# NANO_SIMPLE_walkie-talkie.net
KiCad netlist of a schematic drawn in EAGLE
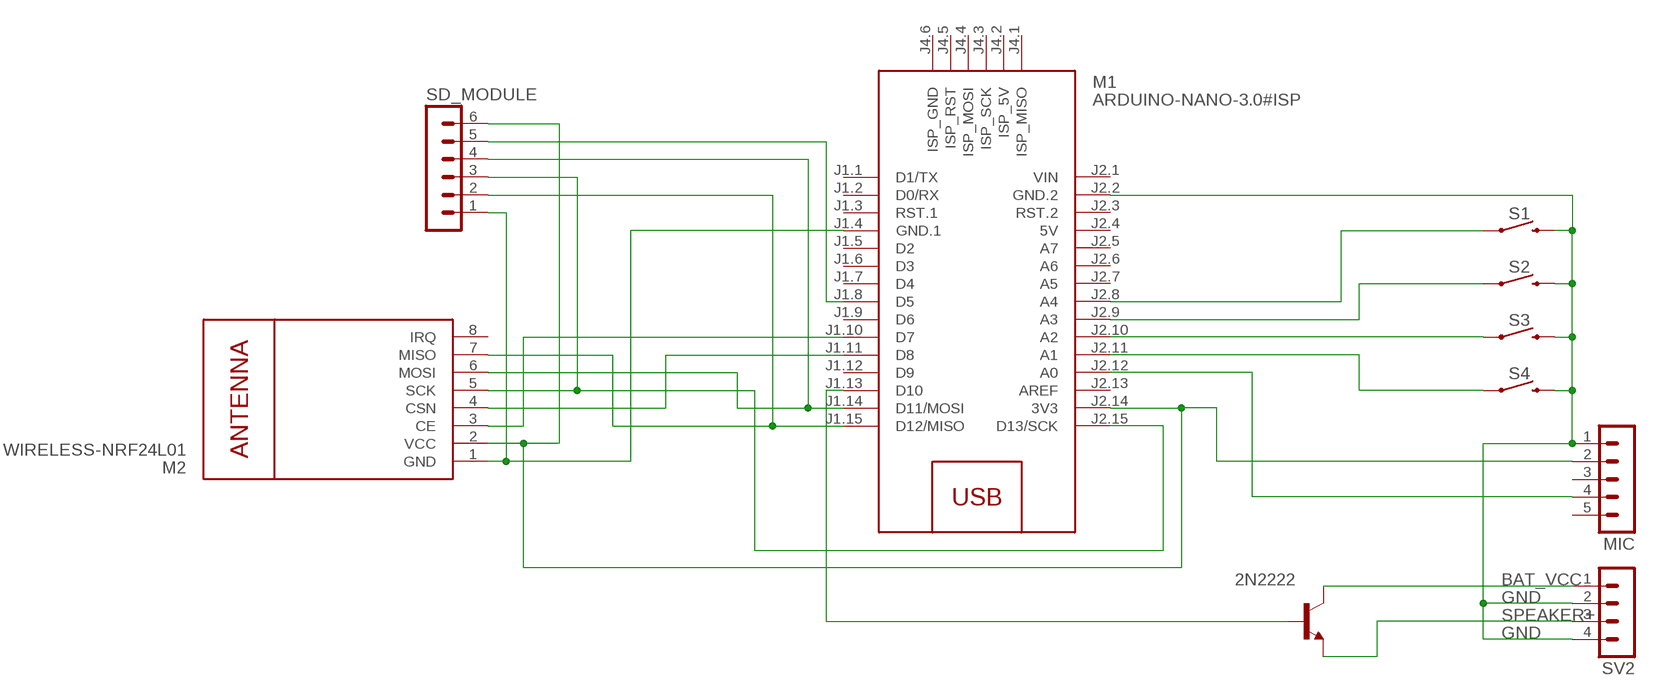
[diagram p0: schematic, sheet 1]

(export (version "E")
  (design (tool "Eeschema 10.0.6"))
  (components
    (comp (ref "M1")
      (value "ARDUINO-NANO-3.0#ISP")
      (footprint "eagle-import:ARDUINO-NANO-3.0#ISP")
      (libsource (lib "eagle-import") (part "ARDUINO-NANO-3.0#ISP"))
    )
    (comp (ref "M2")
      (value "WIRELESS-NRF24L01")
      (footprint "eagle-import:WIRELESS-NRF24L01")
      (libsource (lib "eagle-import") (part "WIRELESS-NRF24L01"))
    )
    (comp (ref "MIC")
      (value "MA05-1")
      (footprint "eagle-import:MA05-1")
      (libsource (lib "eagle-import") (part "MA05-1"))
    )
    (comp (ref "S1")
      (value "MOMENTARY-SWITCH-SPST-PTH-6.0MM")
      (footprint "eagle-import:TACTILE_SWITCH_PTH_6.0MM")
      (libsource (lib "eagle-import") (part "MOMENTARY-SWITCH-SPST-PTH-6.0MM"))
    )
    (comp (ref "S2")
      (value "MOMENTARY-SWITCH-SPST-PTH-6.0MM")
      (footprint "eagle-import:TACTILE_SWITCH_PTH_6.0MM")
      (libsource (lib "eagle-import") (part "MOMENTARY-SWITCH-SPST-PTH-6.0MM"))
    )
    (comp (ref "S3")
      (value "MOMENTARY-SWITCH-SPST-PTH-6.0MM")
      (footprint "eagle-import:TACTILE_SWITCH_PTH_6.0MM")
      (libsource (lib "eagle-import") (part "MOMENTARY-SWITCH-SPST-PTH-6.0MM"))
    )
    (comp (ref "S4")
      (value "MOMENTARY-SWITCH-SPST-PTH-6.0MM")
      (footprint "eagle-import:TACTILE_SWITCH_PTH_6.0MM")
      (libsource (lib "eagle-import") (part "MOMENTARY-SWITCH-SPST-PTH-6.0MM"))
    )
    (comp (ref "SD_MODULE")
      (value "MA06-1")
      (footprint "eagle-import:MA06-1")
      (libsource (lib "eagle-import") (part "MA06-1"))
    )
    (comp (ref "SV2")
      (value "MA04-1")
      (footprint "eagle-import:MA04-1")
      (libsource (lib "eagle-import") (part "MA04-1"))
    )
    (comp (ref "T1")
      (value "2N2222")
      (footprint "eagle-import:TO18")
      (libsource (lib "eagle-import") (part "2N2222"))
    )
  )
  (nets
    (net (code "1") (name "/5V") (class "Default")
      (node (ref "M1") (pin "J2.4") (pinfunction "5V_J2.4") (pintype "power_in"))
    )
    (net (code "2") (name "/BAT_VCC") (class "Default")
      (node (ref "SV2") (pin "1") (pinfunction "1_1") (pintype "passive"))
      (node (ref "T1") (pin "3") (pinfunction "C_3") (pintype "passive"))
    )
    (net (code "3") (name "/GND") (class "Default")
      (node (ref "M1") (pin "J2.2") (pinfunction "GND.2_J2.2") (pintype "power_in"))
      (node (ref "MIC") (pin "1") (pinfunction "1_1") (pintype "passive"))
      (node (ref "S1") (pin "3") (pinfunction "2_3") (pintype "passive"))
      (node (ref "S2") (pin "3") (pinfunction "2_3") (pintype "passive"))
      (node (ref "S3") (pin "3") (pinfunction "2_3") (pintype "passive"))
      (node (ref "S4") (pin "3") (pinfunction "2_3") (pintype "passive"))
      (node (ref "SV2") (pin "2") (pinfunction "2_2") (pintype "passive"))
      (node (ref "SV2") (pin "4") (pinfunction "4_4") (pintype "passive"))
    )
    (net (code "4") (name "/SPEAKER+") (class "Default")
      (node (ref "SV2") (pin "3") (pinfunction "3_3") (pintype "passive"))
      (node (ref "T1") (pin "1") (pinfunction "E_1") (pintype "passive"))
    )
    (net (code "5") (name "/VIN") (class "Default")
      (node (ref "M1") (pin "J2.1") (pinfunction "VIN_J2.1") (pintype "power_in"))
    )
    (net (code "6") (name "Net-(M1-3V3)") (class "Default")
      (node (ref "M1") (pin "J2.14") (pinfunction "3V3_J2.14") (pintype "power_in"))
      (node (ref "M2") (pin "2") (pinfunction "VCC_2") (pintype "power_in"))
      (node (ref "MIC") (pin "2") (pinfunction "2_2") (pintype "passive"))
      (node (ref "SD_MODULE") (pin "6") (pinfunction "6_6") (pintype "passive"))
    )
    (net (code "7") (name "Net-(M1-A0)") (class "Default")
      (node (ref "M1") (pin "J2.12") (pinfunction "A0_J2.12") (pintype "bidirectional"))
      (node (ref "MIC") (pin "4") (pinfunction "4_4") (pintype "passive"))
    )
    (net (code "8") (name "Net-(M1-A1)") (class "Default")
      (node (ref "M1") (pin "J2.11") (pinfunction "A1_J2.11") (pintype "bidirectional"))
      (node (ref "S4") (pin "1") (pinfunction "1_1") (pintype "passive"))
    )
    (net (code "9") (name "Net-(M1-A2)") (class "Default")
      (node (ref "M1") (pin "J2.10") (pinfunction "A2_J2.10") (pintype "bidirectional"))
      (node (ref "S3") (pin "1") (pinfunction "1_1") (pintype "passive"))
    )
    (net (code "10") (name "Net-(M1-A3)") (class "Default")
      (node (ref "M1") (pin "J2.9") (pinfunction "A3_J2.9") (pintype "bidirectional"))
      (node (ref "S2") (pin "1") (pinfunction "1_1") (pintype "passive"))
    )
    (net (code "11") (name "Net-(M1-A4)") (class "Default")
      (node (ref "M1") (pin "J2.8") (pinfunction "A4_J2.8") (pintype "bidirectional"))
      (node (ref "S1") (pin "1") (pinfunction "1_1") (pintype "passive"))
    )
    (net (code "12") (name "Net-(M1-D5)") (class "Default")
      (node (ref "M1") (pin "J1.8") (pinfunction "D5_J1.8") (pintype "bidirectional"))
      (node (ref "SD_MODULE") (pin "5") (pinfunction "5_5") (pintype "passive"))
    )
    (net (code "13") (name "Net-(M1-D7)") (class "Default")
      (node (ref "M1") (pin "J1.10") (pinfunction "D7_J1.10") (pintype "bidirectional"))
      (node (ref "M2") (pin "3") (pinfunction "CE_3") (pintype "bidirectional"))
    )
    (net (code "14") (name "Net-(M1-D8)") (class "Default")
      (node (ref "M1") (pin "J1.11") (pinfunction "D8_J1.11") (pintype "bidirectional"))
      (node (ref "M2") (pin "4") (pinfunction "CSN_4") (pintype "bidirectional"))
    )
    (net (code "15") (name "Net-(M1-D10)") (class "Default")
      (node (ref "M1") (pin "J1.13") (pinfunction "D10_J1.13") (pintype "bidirectional"))
      (node (ref "T1") (pin "2") (pinfunction "B_2") (pintype "passive"))
    )
    (net (code "16") (name "Net-(M1-D11{slash}MOSI)") (class "Default")
      (node (ref "M1") (pin "J1.14") (pinfunction "D11/MOSI_J1.14") (pintype "bidirectional"))
      (node (ref "M2") (pin "6") (pinfunction "MOSI_6") (pintype "bidirectional"))
      (node (ref "SD_MODULE") (pin "4") (pinfunction "4_4") (pintype "passive"))
    )
    (net (code "17") (name "Net-(M1-D12{slash}MISO)") (class "Default")
      (node (ref "M1") (pin "J1.15") (pinfunction "D12/MISO_J1.15") (pintype "bidirectional"))
      (node (ref "M2") (pin "7") (pinfunction "MISO_7") (pintype "bidirectional"))
      (node (ref "SD_MODULE") (pin "2") (pinfunction "2_2") (pintype "passive"))
    )
    (net (code "18") (name "Net-(M1-D13{slash}SCK)") (class "Default")
      (node (ref "M1") (pin "J2.15") (pinfunction "D13/SCK_J2.15") (pintype "bidirectional"))
      (node (ref "M2") (pin "5") (pinfunction "SCK_5") (pintype "bidirectional"))
      (node (ref "SD_MODULE") (pin "3") (pinfunction "3_3") (pintype "passive"))
    )
    (net (code "19") (name "Net-(M1-GND.1)") (class "Default")
      (node (ref "M1") (pin "J1.4") (pinfunction "GND.1_J1.4") (pintype "power_in"))
      (node (ref "M2") (pin "1") (pinfunction "GND_1") (pintype "power_in"))
      (node (ref "SD_MODULE") (pin "1") (pinfunction "1_1") (pintype "passive"))
    )
    (net (code "20") (name "unconnected-(M1-A5-PadJ2.7)") (class "Default")
      (node (ref "M1") (pin "J2.7") (pinfunction "A5_J2.7") (pintype "bidirectional"))
    )
    (net (code "21") (name "unconnected-(M1-A6-PadJ2.6)") (class "Default")
      (node (ref "M1") (pin "J2.6") (pinfunction "A6_J2.6") (pintype "bidirectional"))
    )
    (net (code "22") (name "unconnected-(M1-A7-PadJ2.5)") (class "Default")
      (node (ref "M1") (pin "J2.5") (pinfunction "A7_J2.5") (pintype "bidirectional"))
    )
    (net (code "23") (name "unconnected-(M1-AREF-PadJ2.13)") (class "Default")
      (node (ref "M1") (pin "J2.13") (pinfunction "AREF_J2.13") (pintype "bidirectional"))
    )
    (net (code "24") (name "unconnected-(M1-D0{slash}RX-PadJ1.2)") (class "Default")
      (node (ref "M1") (pin "J1.2") (pinfunction "D0/RX_J1.2") (pintype "bidirectional"))
    )
    (net (code "25") (name "unconnected-(M1-D1{slash}TX-PadJ1.1)") (class "Default")
      (node (ref "M1") (pin "J1.1") (pinfunction "D1/TX_J1.1") (pintype "bidirectional"))
    )
    (net (code "26") (name "unconnected-(M1-D2-PadJ1.5)") (class "Default")
      (node (ref "M1") (pin "J1.5") (pinfunction "D2_J1.5") (pintype "bidirectional"))
    )
    (net (code "27") (name "unconnected-(M1-D3-PadJ1.6)") (class "Default")
      (node (ref "M1") (pin "J1.6") (pinfunction "D3_J1.6") (pintype "bidirectional"))
    )
    (net (code "28") (name "unconnected-(M1-D4-PadJ1.7)") (class "Default")
      (node (ref "M1") (pin "J1.7") (pinfunction "D4_J1.7") (pintype "bidirectional"))
    )
    (net (code "29") (name "unconnected-(M1-D6-PadJ1.9)") (class "Default")
      (node (ref "M1") (pin "J1.9") (pinfunction "D6_J1.9") (pintype "bidirectional"))
    )
    (net (code "30") (name "unconnected-(M1-D9-PadJ1.12)") (class "Default")
      (node (ref "M1") (pin "J1.12") (pinfunction "D9_J1.12") (pintype "bidirectional"))
    )
    (net (code "31") (name "unconnected-(M1-ISP_5V-PadJ4.2)") (class "Default")
      (node (ref "M1") (pin "J4.2") (pinfunction "ISP_5V_J4.2") (pintype "bidirectional"))
    )
    (net (code "32") (name "unconnected-(M1-ISP_GND-PadJ4.6)") (class "Default")
      (node (ref "M1") (pin "J4.6") (pinfunction "ISP_GND_J4.6") (pintype "bidirectional"))
    )
    (net (code "33") (name "unconnected-(M1-ISP_MISO-PadJ4.1)") (class "Default")
      (node (ref "M1") (pin "J4.1") (pinfunction "ISP_MISO_J4.1") (pintype "bidirectional"))
    )
    (net (code "34") (name "unconnected-(M1-ISP_MOSI-PadJ4.4)") (class "Default")
      (node (ref "M1") (pin "J4.4") (pinfunction "ISP_MOSI_J4.4") (pintype "bidirectional"))
    )
    (net (code "35") (name "unconnected-(M1-ISP_RST-PadJ4.5)") (class "Default")
      (node (ref "M1") (pin "J4.5") (pinfunction "ISP_RST_J4.5") (pintype "bidirectional"))
    )
    (net (code "36") (name "unconnected-(M1-ISP_SCK-PadJ4.3)") (class "Default")
      (node (ref "M1") (pin "J4.3") (pinfunction "ISP_SCK_J4.3") (pintype "bidirectional"))
    )
    (net (code "37") (name "unconnected-(M1-RST.1-PadJ1.3)") (class "Default")
      (node (ref "M1") (pin "J1.3") (pinfunction "RST.1_J1.3") (pintype "bidirectional"))
    )
    (net (code "38") (name "unconnected-(M1-RST.2-PadJ2.3)") (class "Default")
      (node (ref "M1") (pin "J2.3") (pinfunction "RST.2_J2.3") (pintype "bidirectional"))
    )
    (net (code "39") (name "unconnected-(M2-IRQ-Pad8)") (class "Default")
      (node (ref "M2") (pin "8") (pinfunction "IRQ_8") (pintype "bidirectional"))
    )
    (net (code "40") (name "unconnected-(MIC-Pad3)") (class "Default")
      (node (ref "MIC") (pin "3") (pinfunction "3_3") (pintype "passive"))
    )
    (net (code "41") (name "unconnected-(MIC-Pad5)") (class "Default")
      (node (ref "MIC") (pin "5") (pinfunction "5_5") (pintype "passive"))
    )
  )
)
